# Placa_CLP_2021-08-01_15-21-18.net
KiCad netlist of a schematic drawn in EasyEDA
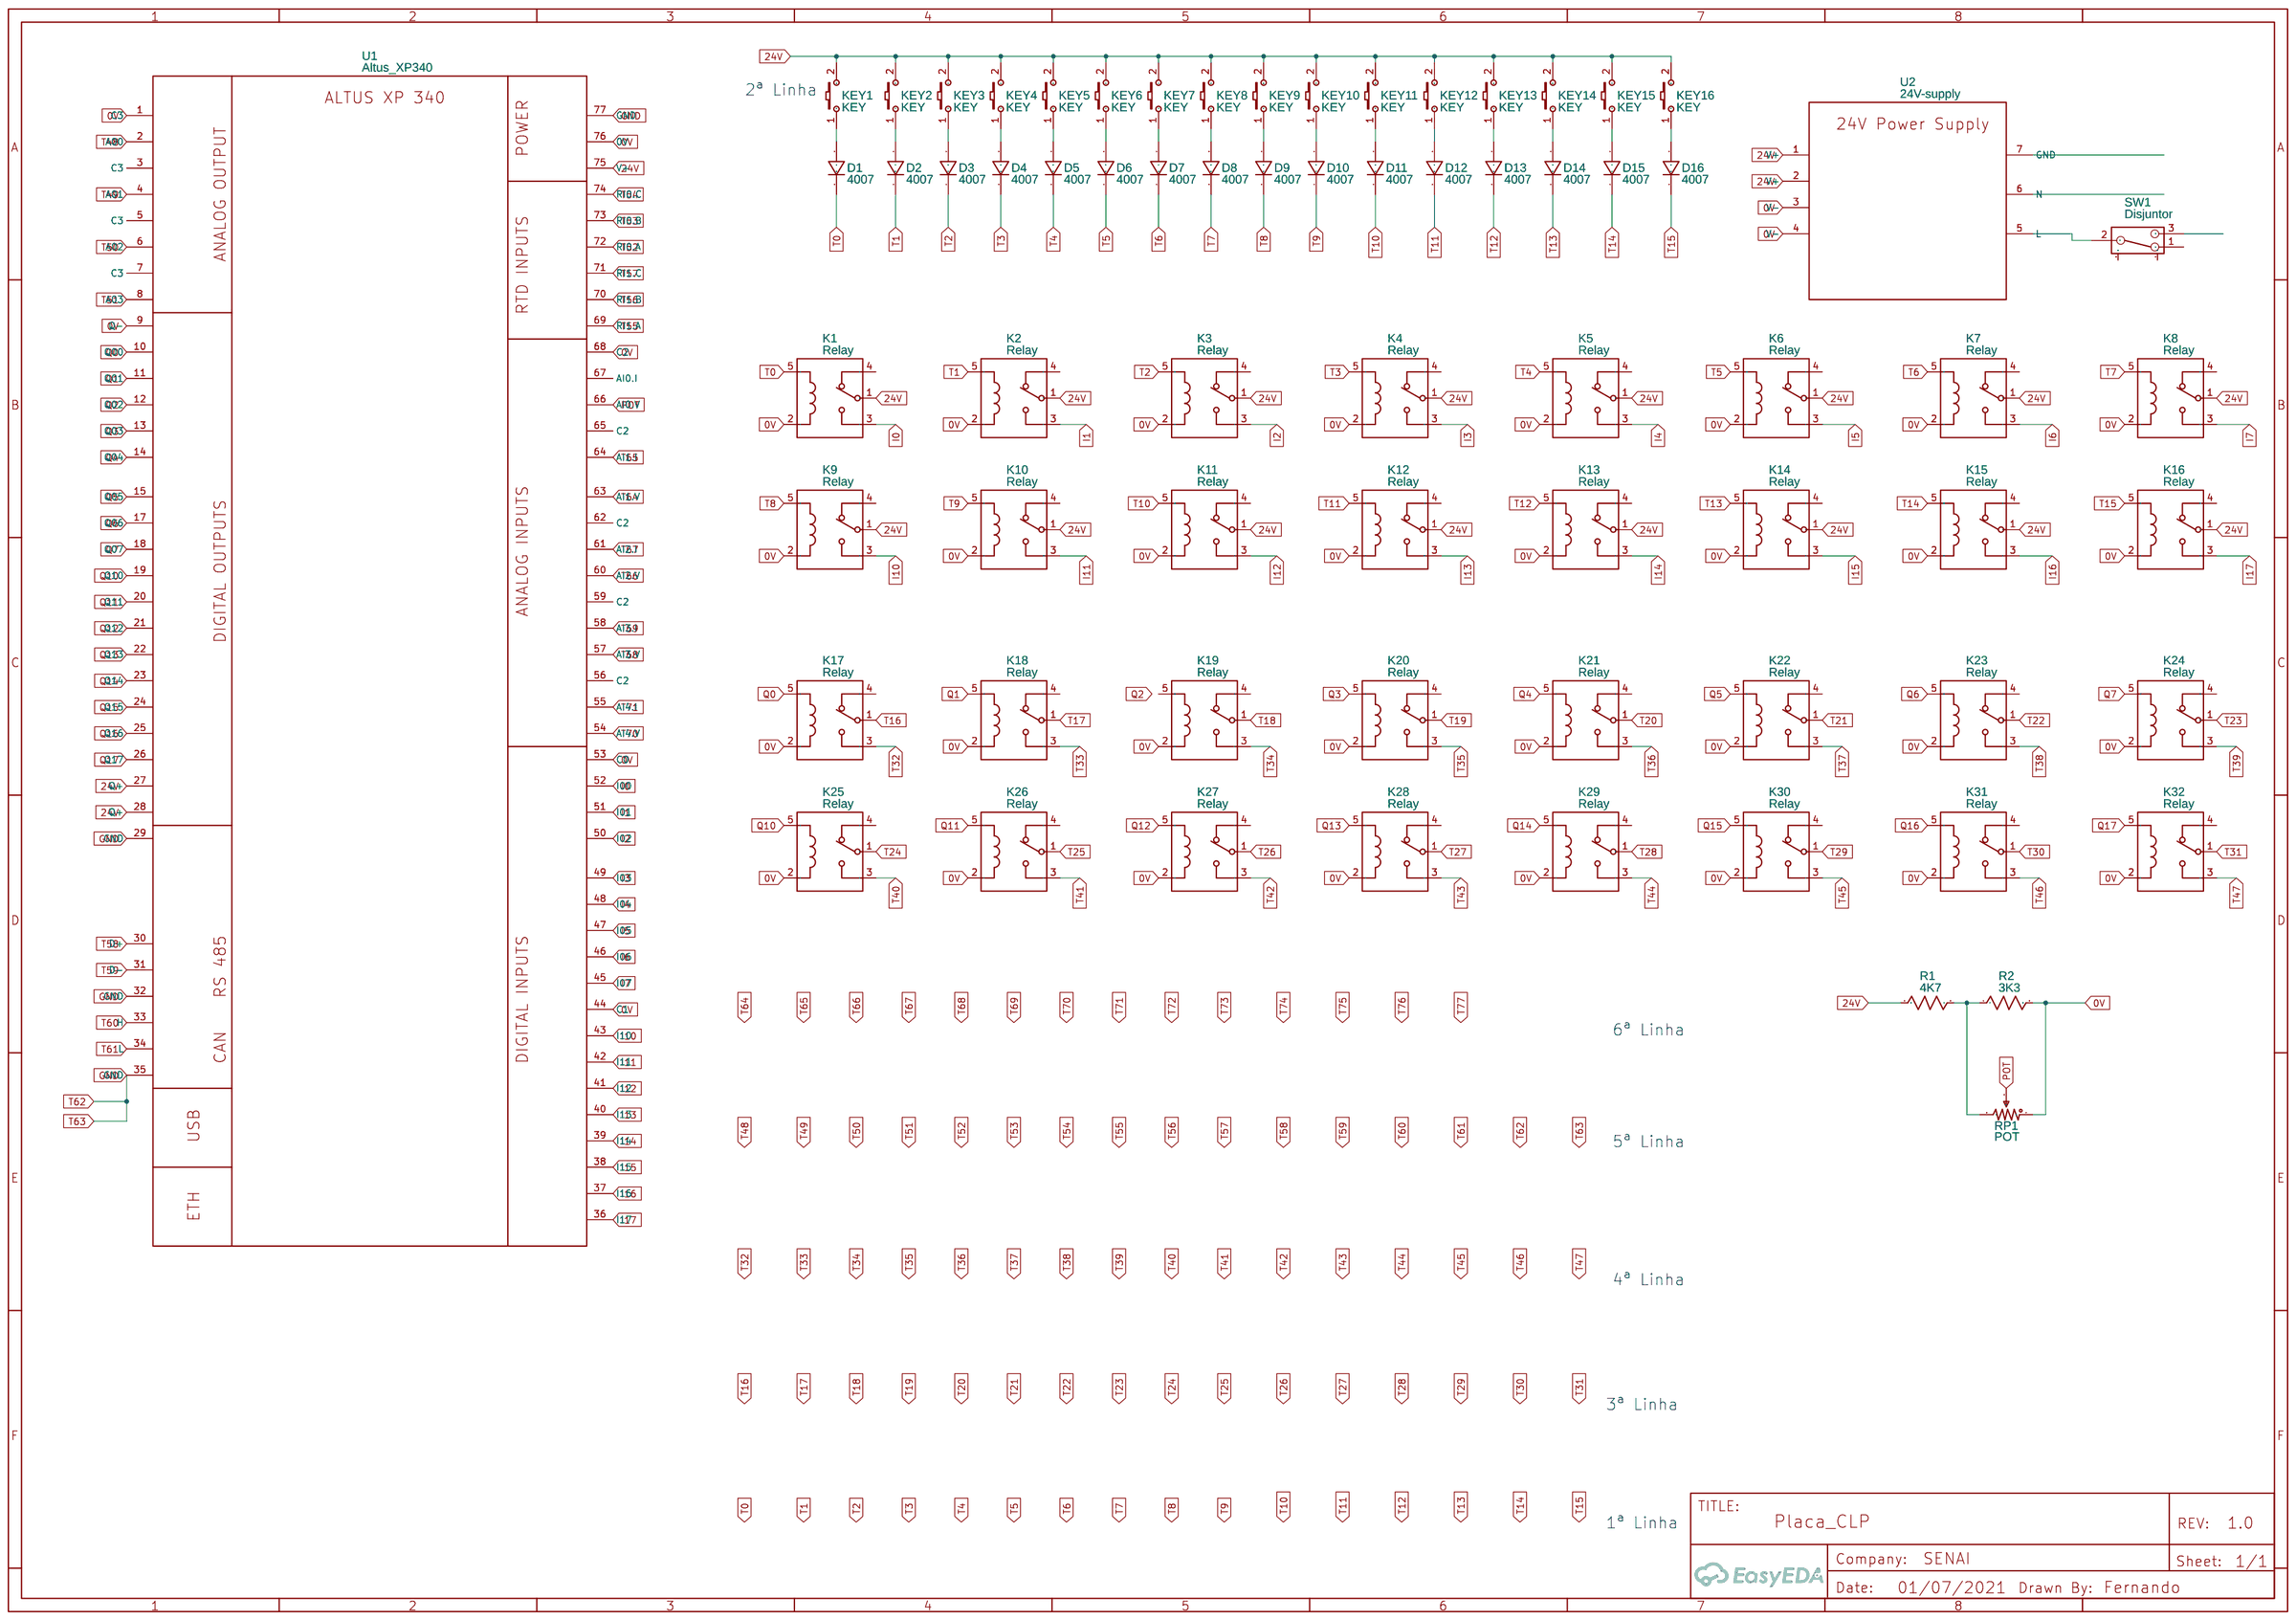
[diagram p0: schematic sheet]

(export (version "E")
  (design (tool "Eeschema 10.0.6"))
  (components
    (comp (ref "D1")
      (value "4007")
      (fields (field (name "BOM_Manufacturer Part") "1N4007") (field (name "BOM_Supplier Part") "C106903"))
      (libsource (lib "") (part "1N4007"))
    )
    (comp (ref "D2")
      (value "4007")
      (fields (field (name "BOM_Manufacturer Part") "1N4007") (field (name "BOM_Supplier Part") "C106903"))
      (libsource (lib "") (part "1N4007"))
    )
    (comp (ref "D3")
      (value "4007")
      (fields (field (name "BOM_Manufacturer Part") "1N4007") (field (name "BOM_Supplier Part") "C106903"))
      (libsource (lib "") (part "1N4007"))
    )
    (comp (ref "D4")
      (value "4007")
      (fields (field (name "BOM_Manufacturer Part") "1N4007") (field (name "BOM_Supplier Part") "C106903"))
      (libsource (lib "") (part "1N4007"))
    )
    (comp (ref "D5")
      (value "4007")
      (fields (field (name "BOM_Manufacturer Part") "1N4007") (field (name "BOM_Supplier Part") "C106903"))
      (libsource (lib "") (part "1N4007"))
    )
    (comp (ref "D6")
      (value "4007")
      (fields (field (name "BOM_Manufacturer Part") "1N4007") (field (name "BOM_Supplier Part") "C106903"))
      (libsource (lib "") (part "1N4007"))
    )
    (comp (ref "D7")
      (value "4007")
      (fields (field (name "BOM_Manufacturer Part") "1N4007") (field (name "BOM_Supplier Part") "C106903"))
      (libsource (lib "") (part "1N4007"))
    )
    (comp (ref "D8")
      (value "4007")
      (fields (field (name "BOM_Manufacturer Part") "1N4007") (field (name "BOM_Supplier Part") "C106903"))
      (libsource (lib "") (part "1N4007"))
    )
    (comp (ref "D9")
      (value "4007")
      (fields (field (name "BOM_Manufacturer Part") "1N4007") (field (name "BOM_Supplier Part") "C106903"))
      (libsource (lib "") (part "1N4007"))
    )
    (comp (ref "D10")
      (value "4007")
      (fields (field (name "BOM_Manufacturer Part") "1N4007") (field (name "BOM_Supplier Part") "C106903"))
      (libsource (lib "") (part "1N4007"))
    )
    (comp (ref "D11")
      (value "4007")
      (fields (field (name "BOM_Manufacturer Part") "1N4007") (field (name "BOM_Supplier Part") "C106903"))
      (libsource (lib "") (part "1N4007"))
    )
    (comp (ref "D12")
      (value "4007")
      (fields (field (name "BOM_Manufacturer Part") "1N4007") (field (name "BOM_Supplier Part") "C106903"))
      (libsource (lib "") (part "1N4007"))
    )
    (comp (ref "D13")
      (value "4007")
      (fields (field (name "BOM_Manufacturer Part") "1N4007") (field (name "BOM_Supplier Part") "C106903"))
      (libsource (lib "") (part "1N4007"))
    )
    (comp (ref "D14")
      (value "4007")
      (fields (field (name "BOM_Manufacturer Part") "1N4007") (field (name "BOM_Supplier Part") "C106903"))
      (libsource (lib "") (part "1N4007"))
    )
    (comp (ref "D15")
      (value "4007")
      (fields (field (name "BOM_Manufacturer Part") "1N4007") (field (name "BOM_Supplier Part") "C106903"))
      (libsource (lib "") (part "1N4007"))
    )
    (comp (ref "D16")
      (value "4007")
      (fields (field (name "BOM_Manufacturer Part") "1N4007") (field (name "BOM_Supplier Part") "C106903"))
      (libsource (lib "") (part "1N4007"))
    )
    (comp (ref "K1")
      (value "Relay")
      (fields
        (field (name "BOM_Manufacturer Part") "RelayHT3F-12VDC-SHG")
        (field (name "BOM_Supplier Part") "C22022")
      )
      (libsource (lib "") (part "RelayHT3F-12VDC-SHG"))
    )
    (comp (ref "K2")
      (value "Relay")
      (fields
        (field (name "BOM_Manufacturer Part") "RelayHT3F-12VDC-SHG")
        (field (name "BOM_Supplier Part") "C22022")
      )
      (libsource (lib "") (part "RelayHT3F-12VDC-SHG"))
    )
    (comp (ref "K3")
      (value "Relay")
      (fields
        (field (name "BOM_Manufacturer Part") "RelayHT3F-12VDC-SHG")
        (field (name "BOM_Supplier Part") "C22022")
      )
      (libsource (lib "") (part "RelayHT3F-12VDC-SHG"))
    )
    (comp (ref "K4")
      (value "Relay")
      (fields
        (field (name "BOM_Manufacturer Part") "RelayHT3F-12VDC-SHG")
        (field (name "BOM_Supplier Part") "C22022")
      )
      (libsource (lib "") (part "RelayHT3F-12VDC-SHG"))
    )
    (comp (ref "K5")
      (value "Relay")
      (fields
        (field (name "BOM_Manufacturer Part") "RelayHT3F-12VDC-SHG")
        (field (name "BOM_Supplier Part") "C22022")
      )
      (libsource (lib "") (part "RelayHT3F-12VDC-SHG"))
    )
    (comp (ref "K6")
      (value "Relay")
      (fields
        (field (name "BOM_Manufacturer Part") "RelayHT3F-12VDC-SHG")
        (field (name "BOM_Supplier Part") "C22022")
      )
      (libsource (lib "") (part "RelayHT3F-12VDC-SHG"))
    )
    (comp (ref "K7")
      (value "Relay")
      (fields
        (field (name "BOM_Manufacturer Part") "RelayHT3F-12VDC-SHG")
        (field (name "BOM_Supplier Part") "C22022")
      )
      (libsource (lib "") (part "RelayHT3F-12VDC-SHG"))
    )
    (comp (ref "K8")
      (value "Relay")
      (fields
        (field (name "BOM_Manufacturer Part") "RelayHT3F-12VDC-SHG")
        (field (name "BOM_Supplier Part") "C22022")
      )
      (libsource (lib "") (part "RelayHT3F-12VDC-SHG"))
    )
    (comp (ref "K9")
      (value "Relay")
      (fields
        (field (name "BOM_Manufacturer Part") "RelayHT3F-12VDC-SHG")
        (field (name "BOM_Supplier Part") "C22022")
      )
      (libsource (lib "") (part "RelayHT3F-12VDC-SHG"))
    )
    (comp (ref "K10")
      (value "Relay")
      (fields
        (field (name "BOM_Manufacturer Part") "RelayHT3F-12VDC-SHG")
        (field (name "BOM_Supplier Part") "C22022")
      )
      (libsource (lib "") (part "RelayHT3F-12VDC-SHG"))
    )
    (comp (ref "K11")
      (value "Relay")
      (fields
        (field (name "BOM_Manufacturer Part") "RelayHT3F-12VDC-SHG")
        (field (name "BOM_Supplier Part") "C22022")
      )
      (libsource (lib "") (part "RelayHT3F-12VDC-SHG"))
    )
    (comp (ref "K12")
      (value "Relay")
      (fields
        (field (name "BOM_Manufacturer Part") "RelayHT3F-12VDC-SHG")
        (field (name "BOM_Supplier Part") "C22022")
      )
      (libsource (lib "") (part "RelayHT3F-12VDC-SHG"))
    )
    (comp (ref "K13")
      (value "Relay")
      (fields
        (field (name "BOM_Manufacturer Part") "RelayHT3F-12VDC-SHG")
        (field (name "BOM_Supplier Part") "C22022")
      )
      (libsource (lib "") (part "RelayHT3F-12VDC-SHG"))
    )
    (comp (ref "K14")
      (value "Relay")
      (fields
        (field (name "BOM_Manufacturer Part") "RelayHT3F-12VDC-SHG")
        (field (name "BOM_Supplier Part") "C22022")
      )
      (libsource (lib "") (part "RelayHT3F-12VDC-SHG"))
    )
    (comp (ref "K15")
      (value "Relay")
      (fields
        (field (name "BOM_Manufacturer Part") "RelayHT3F-12VDC-SHG")
        (field (name "BOM_Supplier Part") "C22022")
      )
      (libsource (lib "") (part "RelayHT3F-12VDC-SHG"))
    )
    (comp (ref "K16")
      (value "Relay")
      (fields
        (field (name "BOM_Manufacturer Part") "RelayHT3F-12VDC-SHG")
        (field (name "BOM_Supplier Part") "C22022")
      )
      (libsource (lib "") (part "RelayHT3F-12VDC-SHG"))
    )
    (comp (ref "K17")
      (value "Relay")
      (fields
        (field (name "BOM_Manufacturer Part") "RelayHT3F-12VDC-SHG")
        (field (name "BOM_Supplier Part") "C22022")
      )
      (libsource (lib "") (part "RelayHT3F-12VDC-SHG"))
    )
    (comp (ref "K18")
      (value "Relay")
      (fields
        (field (name "BOM_Manufacturer Part") "RelayHT3F-12VDC-SHG")
        (field (name "BOM_Supplier Part") "C22022")
      )
      (libsource (lib "") (part "RelayHT3F-12VDC-SHG"))
    )
    (comp (ref "K19")
      (value "Relay")
      (fields
        (field (name "BOM_Manufacturer Part") "RelayHT3F-12VDC-SHG")
        (field (name "BOM_Supplier Part") "C22022")
      )
      (libsource (lib "") (part "RelayHT3F-12VDC-SHG"))
    )
    (comp (ref "K20")
      (value "Relay")
      (fields
        (field (name "BOM_Manufacturer Part") "RelayHT3F-12VDC-SHG")
        (field (name "BOM_Supplier Part") "C22022")
      )
      (libsource (lib "") (part "RelayHT3F-12VDC-SHG"))
    )
    (comp (ref "K21")
      (value "Relay")
      (fields
        (field (name "BOM_Manufacturer Part") "RelayHT3F-12VDC-SHG")
        (field (name "BOM_Supplier Part") "C22022")
      )
      (libsource (lib "") (part "RelayHT3F-12VDC-SHG"))
    )
    (comp (ref "K22")
      (value "Relay")
      (fields
        (field (name "BOM_Manufacturer Part") "RelayHT3F-12VDC-SHG")
        (field (name "BOM_Supplier Part") "C22022")
      )
      (libsource (lib "") (part "RelayHT3F-12VDC-SHG"))
    )
    (comp (ref "K23")
      (value "Relay")
      (fields
        (field (name "BOM_Manufacturer Part") "RelayHT3F-12VDC-SHG")
        (field (name "BOM_Supplier Part") "C22022")
      )
      (libsource (lib "") (part "RelayHT3F-12VDC-SHG"))
    )
    (comp (ref "K24")
      (value "Relay")
      (fields
        (field (name "BOM_Manufacturer Part") "RelayHT3F-12VDC-SHG")
        (field (name "BOM_Supplier Part") "C22022")
      )
      (libsource (lib "") (part "RelayHT3F-12VDC-SHG"))
    )
    (comp (ref "K25")
      (value "Relay")
      (fields
        (field (name "BOM_Manufacturer Part") "RelayHT3F-12VDC-SHG")
        (field (name "BOM_Supplier Part") "C22022")
      )
      (libsource (lib "") (part "RelayHT3F-12VDC-SHG"))
    )
    (comp (ref "K26")
      (value "Relay")
      (fields
        (field (name "BOM_Manufacturer Part") "RelayHT3F-12VDC-SHG")
        (field (name "BOM_Supplier Part") "C22022")
      )
      (libsource (lib "") (part "RelayHT3F-12VDC-SHG"))
    )
    (comp (ref "K27")
      (value "Relay")
      (fields
        (field (name "BOM_Manufacturer Part") "RelayHT3F-12VDC-SHG")
        (field (name "BOM_Supplier Part") "C22022")
      )
      (libsource (lib "") (part "RelayHT3F-12VDC-SHG"))
    )
    (comp (ref "K28")
      (value "Relay")
      (fields
        (field (name "BOM_Manufacturer Part") "RelayHT3F-12VDC-SHG")
        (field (name "BOM_Supplier Part") "C22022")
      )
      (libsource (lib "") (part "RelayHT3F-12VDC-SHG"))
    )
    (comp (ref "K29")
      (value "Relay")
      (fields
        (field (name "BOM_Manufacturer Part") "RelayHT3F-12VDC-SHG")
        (field (name "BOM_Supplier Part") "C22022")
      )
      (libsource (lib "") (part "RelayHT3F-12VDC-SHG"))
    )
    (comp (ref "K30")
      (value "Relay")
      (fields
        (field (name "BOM_Manufacturer Part") "RelayHT3F-12VDC-SHG")
        (field (name "BOM_Supplier Part") "C22022")
      )
      (libsource (lib "") (part "RelayHT3F-12VDC-SHG"))
    )
    (comp (ref "K31")
      (value "Relay")
      (fields
        (field (name "BOM_Manufacturer Part") "RelayHT3F-12VDC-SHG")
        (field (name "BOM_Supplier Part") "C22022")
      )
      (libsource (lib "") (part "RelayHT3F-12VDC-SHG"))
    )
    (comp (ref "K32")
      (value "Relay")
      (fields
        (field (name "BOM_Manufacturer Part") "RelayHT3F-12VDC-SHG")
        (field (name "BOM_Supplier Part") "C22022")
      )
      (libsource (lib "") (part "RelayHT3F-12VDC-SHG"))
    )
    (comp (ref "KEY1")
      (value "KEY")
      (fields
        (field (name "BOM_Manufacturer Part") "K2-1107ST-A4SW-06")
        (field (name "BOM_Supplier Part") "C118141")
      )
      (libsource (lib "") (part "K2-3.6×6.1_SMD"))
    )
    (comp (ref "KEY2")
      (value "KEY")
      (fields
        (field (name "BOM_Manufacturer Part") "K2-1107ST-A4SW-06")
        (field (name "BOM_Supplier Part") "C118141")
      )
      (libsource (lib "") (part "K2-3.6×6.1_SMD"))
    )
    (comp (ref "KEY3")
      (value "KEY")
      (fields
        (field (name "BOM_Manufacturer Part") "K2-1107ST-A4SW-06")
        (field (name "BOM_Supplier Part") "C118141")
      )
      (libsource (lib "") (part "K2-3.6×6.1_SMD"))
    )
    (comp (ref "KEY4")
      (value "KEY")
      (fields
        (field (name "BOM_Manufacturer Part") "K2-1107ST-A4SW-06")
        (field (name "BOM_Supplier Part") "C118141")
      )
      (libsource (lib "") (part "K2-3.6×6.1_SMD"))
    )
    (comp (ref "KEY5")
      (value "KEY")
      (fields
        (field (name "BOM_Manufacturer Part") "K2-1107ST-A4SW-06")
        (field (name "BOM_Supplier Part") "C118141")
      )
      (libsource (lib "") (part "K2-3.6×6.1_SMD"))
    )
    (comp (ref "KEY6")
      (value "KEY")
      (fields
        (field (name "BOM_Manufacturer Part") "K2-1107ST-A4SW-06")
        (field (name "BOM_Supplier Part") "C118141")
      )
      (libsource (lib "") (part "K2-3.6×6.1_SMD"))
    )
    (comp (ref "KEY7")
      (value "KEY")
      (fields
        (field (name "BOM_Manufacturer Part") "K2-1107ST-A4SW-06")
        (field (name "BOM_Supplier Part") "C118141")
      )
      (libsource (lib "") (part "K2-3.6×6.1_SMD"))
    )
    (comp (ref "KEY8")
      (value "KEY")
      (fields
        (field (name "BOM_Manufacturer Part") "K2-1107ST-A4SW-06")
        (field (name "BOM_Supplier Part") "C118141")
      )
      (libsource (lib "") (part "K2-3.6×6.1_SMD"))
    )
    (comp (ref "KEY9")
      (value "KEY")
      (fields
        (field (name "BOM_Manufacturer Part") "K2-1107ST-A4SW-06")
        (field (name "BOM_Supplier Part") "C118141")
      )
      (libsource (lib "") (part "K2-3.6×6.1_SMD"))
    )
    (comp (ref "KEY10")
      (value "KEY")
      (fields
        (field (name "BOM_Manufacturer Part") "K2-1107ST-A4SW-06")
        (field (name "BOM_Supplier Part") "C118141")
      )
      (libsource (lib "") (part "K2-3.6×6.1_SMD"))
    )
    (comp (ref "KEY11")
      (value "KEY")
      (fields
        (field (name "BOM_Manufacturer Part") "K2-1107ST-A4SW-06")
        (field (name "BOM_Supplier Part") "C118141")
      )
      (libsource (lib "") (part "K2-3.6×6.1_SMD"))
    )
    (comp (ref "KEY12")
      (value "KEY")
      (fields
        (field (name "BOM_Manufacturer Part") "K2-1107ST-A4SW-06")
        (field (name "BOM_Supplier Part") "C118141")
      )
      (libsource (lib "") (part "K2-3.6×6.1_SMD"))
    )
    (comp (ref "KEY13")
      (value "KEY")
      (fields
        (field (name "BOM_Manufacturer Part") "K2-1107ST-A4SW-06")
        (field (name "BOM_Supplier Part") "C118141")
      )
      (libsource (lib "") (part "K2-3.6×6.1_SMD"))
    )
    (comp (ref "KEY14")
      (value "KEY")
      (fields
        (field (name "BOM_Manufacturer Part") "K2-1107ST-A4SW-06")
        (field (name "BOM_Supplier Part") "C118141")
      )
      (libsource (lib "") (part "K2-3.6×6.1_SMD"))
    )
    (comp (ref "KEY15")
      (value "KEY")
      (fields
        (field (name "BOM_Manufacturer Part") "K2-1107ST-A4SW-06")
        (field (name "BOM_Supplier Part") "C118141")
      )
      (libsource (lib "") (part "K2-3.6×6.1_SMD"))
    )
    (comp (ref "KEY16")
      (value "KEY")
      (fields
        (field (name "BOM_Manufacturer Part") "K2-1107ST-A4SW-06")
        (field (name "BOM_Supplier Part") "C118141")
      )
      (libsource (lib "") (part "K2-3.6×6.1_SMD"))
    )
    (comp (ref "R1") (value "4K7") (libsource (lib "") (part "R_0603_US")))
    (comp (ref "R2") (value "3K3") (libsource (lib "") (part "R_0603_US")))
    (comp (ref "RP1") (value "POT") (libsource (lib "") (part "R_3386P_US")))
    (comp (ref "SW1")
      (value "Disjuntor")
      (fields
        (field (name "BOM_Manufacturer Part") "SK-12D02-VG5")
        (field (name "BOM_Supplier Part") "C136722")
      )
      (libsource (lib "") (part "SK-12D02-VG5"))
    )
    (comp (ref "U1") (value "Altus_XP340") (libsource (lib "") (part "Altus_XP340")))
    (comp (ref "U2") (value "24V-supply") (libsource (lib "") (part "24V-supply")))
  )
  (nets
    (net (code "1") (name "0V") (class "Default")
      (node (ref "K1") (pin "2") (pinfunction "2_2") (pintype "unspecified"))
      (node (ref "K10") (pin "2") (pinfunction "2_2") (pintype "unspecified"))
      (node (ref "K11") (pin "2") (pinfunction "2_2") (pintype "unspecified"))
      (node (ref "K12") (pin "2") (pinfunction "2_2") (pintype "unspecified"))
      (node (ref "K13") (pin "2") (pinfunction "2_2") (pintype "unspecified"))
      (node (ref "K14") (pin "2") (pinfunction "2_2") (pintype "unspecified"))
      (node (ref "K15") (pin "2") (pinfunction "2_2") (pintype "unspecified"))
      (node (ref "K16") (pin "2") (pinfunction "2_2") (pintype "unspecified"))
      (node (ref "K17") (pin "2") (pinfunction "2_2") (pintype "unspecified"))
      (node (ref "K18") (pin "2") (pinfunction "2_2") (pintype "unspecified"))
      (node (ref "K19") (pin "2") (pinfunction "2_2") (pintype "unspecified"))
      (node (ref "K2") (pin "2") (pinfunction "2_2") (pintype "unspecified"))
      (node (ref "K20") (pin "2") (pinfunction "2_2") (pintype "unspecified"))
      (node (ref "K21") (pin "2") (pinfunction "2_2") (pintype "unspecified"))
      (node (ref "K22") (pin "2") (pinfunction "2_2") (pintype "unspecified"))
      (node (ref "K23") (pin "2") (pinfunction "2_2") (pintype "unspecified"))
      (node (ref "K24") (pin "2") (pinfunction "2_2") (pintype "unspecified"))
      (node (ref "K25") (pin "2") (pinfunction "2_2") (pintype "unspecified"))
      (node (ref "K26") (pin "2") (pinfunction "2_2") (pintype "unspecified"))
      (node (ref "K27") (pin "2") (pinfunction "2_2") (pintype "unspecified"))
      (node (ref "K28") (pin "2") (pinfunction "2_2") (pintype "unspecified"))
      (node (ref "K29") (pin "2") (pinfunction "2_2") (pintype "unspecified"))
      (node (ref "K3") (pin "2") (pinfunction "2_2") (pintype "unspecified"))
      (node (ref "K30") (pin "2") (pinfunction "2_2") (pintype "unspecified"))
      (node (ref "K31") (pin "2") (pinfunction "2_2") (pintype "unspecified"))
      (node (ref "K32") (pin "2") (pinfunction "2_2") (pintype "unspecified"))
      (node (ref "K4") (pin "2") (pinfunction "2_2") (pintype "unspecified"))
      (node (ref "K5") (pin "2") (pinfunction "2_2") (pintype "unspecified"))
      (node (ref "K6") (pin "2") (pinfunction "2_2") (pintype "unspecified"))
      (node (ref "K7") (pin "2") (pinfunction "2_2") (pintype "unspecified"))
      (node (ref "K8") (pin "2") (pinfunction "2_2") (pintype "unspecified"))
      (node (ref "K9") (pin "2") (pinfunction "2_2") (pintype "unspecified"))
      (node (ref "R2") (pin "2") (pinfunction "2_2") (pintype "unspecified"))
      (node (ref "RP1") (pin "1") (pinfunction "1_1") (pintype "unspecified"))
    )
    (net (code "2") (name "24V") (class "Default")
      (node (ref "K1") (pin "1") (pinfunction "1_1") (pintype "unspecified"))
      (node (ref "K10") (pin "1") (pinfunction "1_1") (pintype "unspecified"))
      (node (ref "K11") (pin "1") (pinfunction "1_1") (pintype "unspecified"))
      (node (ref "K12") (pin "1") (pinfunction "1_1") (pintype "unspecified"))
      (node (ref "K13") (pin "1") (pinfunction "1_1") (pintype "unspecified"))
      (node (ref "K14") (pin "1") (pinfunction "1_1") (pintype "unspecified"))
      (node (ref "K15") (pin "1") (pinfunction "1_1") (pintype "unspecified"))
      (node (ref "K16") (pin "1") (pinfunction "1_1") (pintype "unspecified"))
      (node (ref "K2") (pin "1") (pinfunction "1_1") (pintype "unspecified"))
      (node (ref "K3") (pin "1") (pinfunction "1_1") (pintype "unspecified"))
      (node (ref "K4") (pin "1") (pinfunction "1_1") (pintype "unspecified"))
      (node (ref "K5") (pin "1") (pinfunction "1_1") (pintype "unspecified"))
      (node (ref "K6") (pin "1") (pinfunction "1_1") (pintype "unspecified"))
      (node (ref "K7") (pin "1") (pinfunction "1_1") (pintype "unspecified"))
      (node (ref "K8") (pin "1") (pinfunction "1_1") (pintype "unspecified"))
      (node (ref "K9") (pin "1") (pinfunction "1_1") (pintype "unspecified"))
      (node (ref "KEY1") (pin "2") (pinfunction "2_2") (pintype "unspecified"))
      (node (ref "KEY10") (pin "2") (pinfunction "2_2") (pintype "unspecified"))
      (node (ref "KEY11") (pin "2") (pinfunction "2_2") (pintype "unspecified"))
      (node (ref "KEY12") (pin "2") (pinfunction "2_2") (pintype "unspecified"))
      (node (ref "KEY13") (pin "2") (pinfunction "2_2") (pintype "unspecified"))
      (node (ref "KEY14") (pin "2") (pinfunction "2_2") (pintype "unspecified"))
      (node (ref "KEY15") (pin "2") (pinfunction "2_2") (pintype "unspecified"))
      (node (ref "KEY16") (pin "2") (pinfunction "2_2") (pintype "unspecified"))
      (node (ref "KEY2") (pin "2") (pinfunction "2_2") (pintype "unspecified"))
      (node (ref "KEY3") (pin "2") (pinfunction "2_2") (pintype "unspecified"))
      (node (ref "KEY4") (pin "2") (pinfunction "2_2") (pintype "unspecified"))
      (node (ref "KEY5") (pin "2") (pinfunction "2_2") (pintype "unspecified"))
      (node (ref "KEY6") (pin "2") (pinfunction "2_2") (pintype "unspecified"))
      (node (ref "KEY7") (pin "2") (pinfunction "2_2") (pintype "unspecified"))
      (node (ref "KEY8") (pin "2") (pinfunction "2_2") (pintype "unspecified"))
      (node (ref "KEY9") (pin "2") (pinfunction "2_2") (pintype "unspecified"))
      (node (ref "R1") (pin "1") (pinfunction "1_1") (pintype "unspecified"))
    )
    (net (code "4") (name "I0") (class "Default")
      (node (ref "K1") (pin "3") (pinfunction "3_3") (pintype "unspecified"))
    )
    (net (code "5") (name "I1") (class "Default")
      (node (ref "K2") (pin "3") (pinfunction "3_3") (pintype "unspecified"))
    )
    (net (code "6") (name "I2") (class "Default")
      (node (ref "K3") (pin "3") (pinfunction "3_3") (pintype "unspecified"))
    )
    (net (code "7") (name "I3") (class "Default")
      (node (ref "K4") (pin "3") (pinfunction "3_3") (pintype "unspecified"))
    )
    (net (code "8") (name "I4") (class "Default")
      (node (ref "K5") (pin "3") (pinfunction "3_3") (pintype "unspecified"))
    )
    (net (code "9") (name "I5") (class "Default")
      (node (ref "K6") (pin "3") (pinfunction "3_3") (pintype "unspecified"))
    )
    (net (code "10") (name "I6") (class "Default")
      (node (ref "K7") (pin "3") (pinfunction "3_3") (pintype "unspecified"))
    )
    (net (code "11") (name "I7") (class "Default")
      (node (ref "K8") (pin "3") (pinfunction "3_3") (pintype "unspecified"))
    )
    (net (code "12") (name "I10") (class "Default")
      (node (ref "K9") (pin "3") (pinfunction "3_3") (pintype "unspecified"))
    )
    (net (code "13") (name "I11") (class "Default")
      (node (ref "K10") (pin "3") (pinfunction "3_3") (pintype "unspecified"))
    )
    (net (code "14") (name "I12") (class "Default")
      (node (ref "K11") (pin "3") (pinfunction "3_3") (pintype "unspecified"))
    )
    (net (code "15") (name "I13") (class "Default")
      (node (ref "K12") (pin "3") (pinfunction "3_3") (pintype "unspecified"))
    )
    (net (code "16") (name "I14") (class "Default")
      (node (ref "K13") (pin "3") (pinfunction "3_3") (pintype "unspecified"))
    )
    (net (code "17") (name "I15") (class "Default")
      (node (ref "K14") (pin "3") (pinfunction "3_3") (pintype "unspecified"))
    )
    (net (code "18") (name "I16") (class "Default")
      (node (ref "K15") (pin "3") (pinfunction "3_3") (pintype "unspecified"))
    )
    (net (code "19") (name "I17") (class "Default")
      (node (ref "K16") (pin "3") (pinfunction "3_3") (pintype "unspecified"))
    )
    (net (code "20") (name "Net-(D1-Pad2)") (class "Default")
      (node (ref "D1") (pin "2") (pinfunction "2_2") (pintype "unspecified"))
      (node (ref "KEY1") (pin "1") (pinfunction "1_1") (pintype "unspecified"))
    )
    (net (code "21") (name "Net-(D2-Pad2)") (class "Default")
      (node (ref "D2") (pin "2") (pinfunction "2_2") (pintype "unspecified"))
      (node (ref "KEY2") (pin "1") (pinfunction "1_1") (pintype "unspecified"))
    )
    (net (code "22") (name "Net-(D3-Pad2)") (class "Default")
      (node (ref "D3") (pin "2") (pinfunction "2_2") (pintype "unspecified"))
      (node (ref "KEY3") (pin "1") (pinfunction "1_1") (pintype "unspecified"))
    )
    (net (code "23") (name "Net-(D4-Pad2)") (class "Default")
      (node (ref "D4") (pin "2") (pinfunction "2_2") (pintype "unspecified"))
      (node (ref "KEY4") (pin "1") (pinfunction "1_1") (pintype "unspecified"))
    )
    (net (code "24") (name "Net-(D5-Pad2)") (class "Default")
      (node (ref "D5") (pin "2") (pinfunction "2_2") (pintype "unspecified"))
      (node (ref "KEY5") (pin "1") (pinfunction "1_1") (pintype "unspecified"))
    )
    (net (code "25") (name "Net-(D6-Pad2)") (class "Default")
      (node (ref "D6") (pin "2") (pinfunction "2_2") (pintype "unspecified"))
      (node (ref "KEY6") (pin "1") (pinfunction "1_1") (pintype "unspecified"))
    )
    (net (code "26") (name "Net-(D7-Pad2)") (class "Default")
      (node (ref "D7") (pin "2") (pinfunction "2_2") (pintype "unspecified"))
      (node (ref "KEY7") (pin "1") (pinfunction "1_1") (pintype "unspecified"))
    )
    (net (code "27") (name "Net-(D8-Pad2)") (class "Default")
      (node (ref "D8") (pin "2") (pinfunction "2_2") (pintype "unspecified"))
      (node (ref "KEY8") (pin "1") (pinfunction "1_1") (pintype "unspecified"))
    )
    (net (code "28") (name "Net-(D9-Pad2)") (class "Default")
      (node (ref "D9") (pin "2") (pinfunction "2_2") (pintype "unspecified"))
      (node (ref "KEY9") (pin "1") (pinfunction "1_1") (pintype "unspecified"))
    )
    (net (code "29") (name "Net-(D10-Pad2)") (class "Default")
      (node (ref "D10") (pin "2") (pinfunction "2_2") (pintype "unspecified"))
      (node (ref "KEY10") (pin "1") (pinfunction "1_1") (pintype "unspecified"))
    )
    (net (code "30") (name "Net-(D11-Pad2)") (class "Default")
      (node (ref "D11") (pin "2") (pinfunction "2_2") (pintype "unspecified"))
      (node (ref "KEY11") (pin "1") (pinfunction "1_1") (pintype "unspecified"))
    )
    (net (code "31") (name "Net-(D12-Pad2)") (class "Default")
      (node (ref "D12") (pin "2") (pinfunction "2_2") (pintype "unspecified"))
      (node (ref "KEY12") (pin "1") (pinfunction "1_1") (pintype "unspecified"))
    )
    (net (code "32") (name "Net-(D13-Pad2)") (class "Default")
      (node (ref "D13") (pin "2") (pinfunction "2_2") (pintype "unspecified"))
      (node (ref "KEY13") (pin "1") (pinfunction "1_1") (pintype "unspecified"))
    )
    (net (code "33") (name "Net-(D14-Pad2)") (class "Default")
      (node (ref "D14") (pin "2") (pinfunction "2_2") (pintype "unspecified"))
      (node (ref "KEY14") (pin "1") (pinfunction "1_1") (pintype "unspecified"))
    )
    (net (code "34") (name "Net-(D15-Pad2)") (class "Default")
      (node (ref "D15") (pin "2") (pinfunction "2_2") (pintype "unspecified"))
      (node (ref "KEY15") (pin "1") (pinfunction "1_1") (pintype "unspecified"))
    )
    (net (code "35") (name "Net-(D16-Pad2)") (class "Default")
      (node (ref "D16") (pin "2") (pinfunction "2_2") (pintype "unspecified"))
      (node (ref "KEY16") (pin "1") (pinfunction "1_1") (pintype "unspecified"))
    )
    (net (code "36") (name "Net-(R1-Pad2)") (class "Default")
      (node (ref "R1") (pin "2") (pinfunction "2_2") (pintype "unspecified"))
      (node (ref "R2") (pin "1") (pinfunction "1_1") (pintype "unspecified"))
      (node (ref "RP1") (pin "3") (pinfunction "3_3") (pintype "unspecified"))
    )
    (net (code "37") (name "POT") (class "Default")
      (node (ref "RP1") (pin "2") (pinfunction "2_2") (pintype "unspecified"))
    )
    (net (code "38") (name "Q0") (class "Default")
      (node (ref "K17") (pin "5") (pinfunction "5_5") (pintype "unspecified"))
    )
    (net (code "39") (name "Q1") (class "Default")
      (node (ref "K18") (pin "5") (pinfunction "5_5") (pintype "unspecified"))
    )
    (net (code "41") (name "Q3") (class "Default")
      (node (ref "K20") (pin "5") (pinfunction "5_5") (pintype "unspecified"))
    )
    (net (code "42") (name "Q4") (class "Default")
      (node (ref "K21") (pin "5") (pinfunction "5_5") (pintype "unspecified"))
    )
    (net (code "43") (name "Q5") (class "Default")
      (node (ref "K22") (pin "5") (pinfunction "5_5") (pintype "unspecified"))
    )
    (net (code "44") (name "Q6") (class "Default")
      (node (ref "K23") (pin "5") (pinfunction "5_5") (pintype "unspecified"))
    )
    (net (code "45") (name "Q7") (class "Default")
      (node (ref "K24") (pin "5") (pinfunction "5_5") (pintype "unspecified"))
    )
    (net (code "46") (name "Q10") (class "Default")
      (node (ref "K25") (pin "5") (pinfunction "5_5") (pintype "unspecified"))
    )
    (net (code "47") (name "Q11") (class "Default")
      (node (ref "K26") (pin "5") (pinfunction "5_5") (pintype "unspecified"))
    )
    (net (code "48") (name "Q12") (class "Default")
      (node (ref "K27") (pin "5") (pinfunction "5_5") (pintype "unspecified"))
    )
    (net (code "49") (name "Q13") (class "Default")
      (node (ref "K28") (pin "5") (pinfunction "5_5") (pintype "unspecified"))
    )
    (net (code "50") (name "Q14") (class "Default")
      (node (ref "K29") (pin "5") (pinfunction "5_5") (pintype "unspecified"))
    )
    (net (code "51") (name "Q15") (class "Default")
      (node (ref "K30") (pin "5") (pinfunction "5_5") (pintype "unspecified"))
    )
    (net (code "52") (name "Q16") (class "Default")
      (node (ref "K31") (pin "5") (pinfunction "5_5") (pintype "unspecified"))
    )
    (net (code "53") (name "Q17") (class "Default")
      (node (ref "K32") (pin "5") (pinfunction "5_5") (pintype "unspecified"))
    )
    (net (code "54") (name "T0") (class "Default")
      (node (ref "D1") (pin "1") (pinfunction "1_1") (pintype "unspecified"))
      (node (ref "K1") (pin "5") (pinfunction "5_5") (pintype "unspecified"))
    )
    (net (code "55") (name "T1") (class "Default")
      (node (ref "D2") (pin "1") (pinfunction "1_1") (pintype "unspecified"))
      (node (ref "K2") (pin "5") (pinfunction "5_5") (pintype "unspecified"))
    )
    (net (code "56") (name "T2") (class "Default")
      (node (ref "D3") (pin "1") (pinfunction "1_1") (pintype "unspecified"))
      (node (ref "K3") (pin "5") (pinfunction "5_5") (pintype "unspecified"))
    )
    (net (code "57") (name "T3") (class "Default")
      (node (ref "D4") (pin "1") (pinfunction "1_1") (pintype "unspecified"))
      (node (ref "K4") (pin "5") (pinfunction "5_5") (pintype "unspecified"))
    )
    (net (code "58") (name "T4") (class "Default")
      (node (ref "D5") (pin "1") (pinfunction "1_1") (pintype "unspecified"))
      (node (ref "K5") (pin "5") (pinfunction "5_5") (pintype "unspecified"))
    )
    (net (code "59") (name "T5") (class "Default")
      (node (ref "D6") (pin "1") (pinfunction "1_1") (pintype "unspecified"))
      (node (ref "K6") (pin "5") (pinfunction "5_5") (pintype "unspecified"))
    )
    (net (code "60") (name "T6") (class "Default")
      (node (ref "D7") (pin "1") (pinfunction "1_1") (pintype "unspecified"))
      (node (ref "K7") (pin "5") (pinfunction "5_5") (pintype "unspecified"))
    )
    (net (code "61") (name "T7") (class "Default")
      (node (ref "D8") (pin "1") (pinfunction "1_1") (pintype "unspecified"))
      (node (ref "K8") (pin "5") (pinfunction "5_5") (pintype "unspecified"))
    )
    (net (code "62") (name "T8") (class "Default")
      (node (ref "D9") (pin "1") (pinfunction "1_1") (pintype "unspecified"))
      (node (ref "K9") (pin "5") (pinfunction "5_5") (pintype "unspecified"))
    )
    (net (code "63") (name "T9") (class "Default")
      (node (ref "D10") (pin "1") (pinfunction "1_1") (pintype "unspecified"))
      (node (ref "K10") (pin "5") (pinfunction "5_5") (pintype "unspecified"))
    )
    (net (code "64") (name "T10") (class "Default")
      (node (ref "D11") (pin "1") (pinfunction "1_1") (pintype "unspecified"))
      (node (ref "K11") (pin "5") (pinfunction "5_5") (pintype "unspecified"))
    )
    (net (code "65") (name "T11") (class "Default")
      (node (ref "D12") (pin "1") (pinfunction "1_1") (pintype "unspecified"))
      (node (ref "K12") (pin "5") (pinfunction "5_5") (pintype "unspecified"))
    )
    (net (code "66") (name "T12") (class "Default")
      (node (ref "D13") (pin "1") (pinfunction "1_1") (pintype "unspecified"))
      (node (ref "K13") (pin "5") (pinfunction "5_5") (pintype "unspecified"))
    )
    (net (code "67") (name "T13") (class "Default")
      (node (ref "D14") (pin "1") (pinfunction "1_1") (pintype "unspecified"))
      (node (ref "K14") (pin "5") (pinfunction "5_5") (pintype "unspecified"))
    )
    (net (code "68") (name "T14") (class "Default")
      (node (ref "D15") (pin "1") (pinfunction "1_1") (pintype "unspecified"))
      (node (ref "K15") (pin "5") (pinfunction "5_5") (pintype "unspecified"))
    )
    (net (code "69") (name "T15") (class "Default")
      (node (ref "D16") (pin "1") (pinfunction "1_1") (pintype "unspecified"))
      (node (ref "K16") (pin "5") (pinfunction "5_5") (pintype "unspecified"))
    )
    (net (code "70") (name "T16") (class "Default")
      (node (ref "K17") (pin "1") (pinfunction "1_1") (pintype "unspecified"))
    )
    (net (code "71") (name "T17") (class "Default")
      (node (ref "K18") (pin "1") (pinfunction "1_1") (pintype "unspecified"))
    )
    (net (code "72") (name "T18") (class "Default")
      (node (ref "K19") (pin "1") (pinfunction "1_1") (pintype "unspecified"))
    )
    (net (code "73") (name "T19") (class "Default")
      (node (ref "K20") (pin "1") (pinfunction "1_1") (pintype "unspecified"))
    )
    (net (code "74") (name "T20") (class "Default")
      (node (ref "K21") (pin "1") (pinfunction "1_1") (pintype "unspecified"))
    )
    (net (code "75") (name "T21") (class "Default")
      (node (ref "K22") (pin "1") (pinfunction "1_1") (pintype "unspecified"))
    )
    (net (code "76") (name "T22") (class "Default")
      (node (ref "K23") (pin "1") (pinfunction "1_1") (pintype "unspecified"))
    )
    (net (code "77") (name "T23") (class "Default")
      (node (ref "K24") (pin "1") (pinfunction "1_1") (pintype "unspecified"))
    )
    (net (code "78") (name "T24") (class "Default")
      (node (ref "K25") (pin "1") (pinfunction "1_1") (pintype "unspecified"))
    )
    (net (code "79") (name "T25") (class "Default")
      (node (ref "K26") (pin "1") (pinfunction "1_1") (pintype "unspecified"))
    )
    (net (code "80") (name "T26") (class "Default")
      (node (ref "K27") (pin "1") (pinfunction "1_1") (pintype "unspecified"))
    )
    (net (code "81") (name "T27") (class "Default")
      (node (ref "K28") (pin "1") (pinfunction "1_1") (pintype "unspecified"))
    )
    (net (code "82") (name "T28") (class "Default")
      (node (ref "K29") (pin "1") (pinfunction "1_1") (pintype "unspecified"))
    )
    (net (code "83") (name "T29") (class "Default")
      (node (ref "K30") (pin "1") (pinfunction "1_1") (pintype "unspecified"))
    )
    (net (code "84") (name "T30") (class "Default")
      (node (ref "K31") (pin "1") (pinfunction "1_1") (pintype "unspecified"))
    )
    (net (code "85") (name "T31") (class "Default")
      (node (ref "K32") (pin "1") (pinfunction "1_1") (pintype "unspecified"))
    )
    (net (code "86") (name "T32") (class "Default")
      (node (ref "K17") (pin "3") (pinfunction "3_3") (pintype "unspecified"))
    )
    (net (code "87") (name "T33") (class "Default")
      (node (ref "K18") (pin "3") (pinfunction "3_3") (pintype "unspecified"))
    )
    (net (code "88") (name "T34") (class "Default")
      (node (ref "K19") (pin "3") (pinfunction "3_3") (pintype "unspecified"))
    )
    (net (code "89") (name "T35") (class "Default")
      (node (ref "K20") (pin "3") (pinfunction "3_3") (pintype "unspecified"))
    )
    (net (code "90") (name "T36") (class "Default")
      (node (ref "K21") (pin "3") (pinfunction "3_3") (pintype "unspecified"))
    )
    (net (code "91") (name "T37") (class "Default")
      (node (ref "K22") (pin "3") (pinfunction "3_3") (pintype "unspecified"))
    )
    (net (code "92") (name "T38") (class "Default")
      (node (ref "K23") (pin "3") (pinfunction "3_3") (pintype "unspecified"))
    )
    (net (code "93") (name "T39") (class "Default")
      (node (ref "K24") (pin "3") (pinfunction "3_3") (pintype "unspecified"))
    )
    (net (code "94") (name "T40") (class "Default")
      (node (ref "K25") (pin "3") (pinfunction "3_3") (pintype "unspecified"))
    )
    (net (code "95") (name "T41") (class "Default")
      (node (ref "K26") (pin "3") (pinfunction "3_3") (pintype "unspecified"))
    )
    (net (code "96") (name "T42") (class "Default")
      (node (ref "K27") (pin "3") (pinfunction "3_3") (pintype "unspecified"))
    )
    (net (code "97") (name "T43") (class "Default")
      (node (ref "K28") (pin "3") (pinfunction "3_3") (pintype "unspecified"))
    )
    (net (code "98") (name "T44") (class "Default")
      (node (ref "K29") (pin "3") (pinfunction "3_3") (pintype "unspecified"))
    )
    (net (code "99") (name "T45") (class "Default")
      (node (ref "K30") (pin "3") (pinfunction "3_3") (pintype "unspecified"))
    )
    (net (code "100") (name "T46") (class "Default")
      (node (ref "K31") (pin "3") (pinfunction "3_3") (pintype "unspecified"))
    )
    (net (code "101") (name "T47") (class "Default")
      (node (ref "K32") (pin "3") (pinfunction "3_3") (pintype "unspecified"))
    )
    (net (code "130") (name "unconnected-(K1-Pad4)") (class "Default")
      (node (ref "K1") (pin "4") (pinfunction "4_4") (pintype "unspecified"))
    )
    (net (code "131") (name "unconnected-(K2-Pad4)") (class "Default")
      (node (ref "K2") (pin "4") (pinfunction "4_4") (pintype "unspecified"))
    )
    (net (code "132") (name "unconnected-(K3-Pad4)") (class "Default")
      (node (ref "K3") (pin "4") (pinfunction "4_4") (pintype "unspecified"))
    )
    (net (code "133") (name "unconnected-(K4-Pad4)") (class "Default")
      (node (ref "K4") (pin "4") (pinfunction "4_4") (pintype "unspecified"))
    )
    (net (code "134") (name "unconnected-(K5-Pad4)") (class "Default")
      (node (ref "K5") (pin "4") (pinfunction "4_4") (pintype "unspecified"))
    )
    (net (code "135") (name "unconnected-(K6-Pad4)") (class "Default")
      (node (ref "K6") (pin "4") (pinfunction "4_4") (pintype "unspecified"))
    )
    (net (code "136") (name "unconnected-(K7-Pad4)") (class "Default")
      (node (ref "K7") (pin "4") (pinfunction "4_4") (pintype "unspecified"))
    )
    (net (code "137") (name "unconnected-(K8-Pad4)") (class "Default")
      (node (ref "K8") (pin "4") (pinfunction "4_4") (pintype "unspecified"))
    )
    (net (code "138") (name "unconnected-(K9-Pad4)") (class "Default")
      (node (ref "K9") (pin "4") (pinfunction "4_4") (pintype "unspecified"))
    )
    (net (code "139") (name "unconnected-(K10-Pad4)") (class "Default")
      (node (ref "K10") (pin "4") (pinfunction "4_4") (pintype "unspecified"))
    )
    (net (code "140") (name "unconnected-(K11-Pad4)") (class "Default")
      (node (ref "K11") (pin "4") (pinfunction "4_4") (pintype "unspecified"))
    )
    (net (code "141") (name "unconnected-(K12-Pad4)") (class "Default")
      (node (ref "K12") (pin "4") (pinfunction "4_4") (pintype "unspecified"))
    )
    (net (code "142") (name "unconnected-(K13-Pad4)") (class "Default")
      (node (ref "K13") (pin "4") (pinfunction "4_4") (pintype "unspecified"))
    )
    (net (code "143") (name "unconnected-(K14-Pad4)") (class "Default")
      (node (ref "K14") (pin "4") (pinfunction "4_4") (pintype "unspecified"))
    )
    (net (code "144") (name "unconnected-(K15-Pad4)") (class "Default")
      (node (ref "K15") (pin "4") (pinfunction "4_4") (pintype "unspecified"))
    )
    (net (code "145") (name "unconnected-(K16-Pad4)") (class "Default")
      (node (ref "K16") (pin "4") (pinfunction "4_4") (pintype "unspecified"))
    )
    (net (code "146") (name "unconnected-(K17-Pad4)") (class "Default")
      (node (ref "K17") (pin "4") (pinfunction "4_4") (pintype "unspecified"))
    )
    (net (code "147") (name "unconnected-(K18-Pad4)") (class "Default")
      (node (ref "K18") (pin "4") (pinfunction "4_4") (pintype "unspecified"))
    )
    (net (code "148") (name "unconnected-(K19-Pad4)") (class "Default")
      (node (ref "K19") (pin "4") (pinfunction "4_4") (pintype "unspecified"))
    )
    (net (code "149") (name "unconnected-(K19-Pad5)") (class "Default")
      (node (ref "K19") (pin "5") (pinfunction "5_5") (pintype "unspecified"))
    )
    (net (code "150") (name "unconnected-(K20-Pad4)") (class "Default")
      (node (ref "K20") (pin "4") (pinfunction "4_4") (pintype "unspecified"))
    )
    (net (code "151") (name "unconnected-(K21-Pad4)") (class "Default")
      (node (ref "K21") (pin "4") (pinfunction "4_4") (pintype "unspecified"))
    )
    (net (code "152") (name "unconnected-(K22-Pad4)") (class "Default")
      (node (ref "K22") (pin "4") (pinfunction "4_4") (pintype "unspecified"))
    )
    (net (code "153") (name "unconnected-(K23-Pad4)") (class "Default")
      (node (ref "K23") (pin "4") (pinfunction "4_4") (pintype "unspecified"))
    )
    (net (code "154") (name "unconnected-(K24-Pad4)") (class "Default")
      (node (ref "K24") (pin "4") (pinfunction "4_4") (pintype "unspecified"))
    )
    (net (code "155") (name "unconnected-(K25-Pad4)") (class "Default")
      (node (ref "K25") (pin "4") (pinfunction "4_4") (pintype "unspecified"))
    )
    (net (code "156") (name "unconnected-(K26-Pad4)") (class "Default")
      (node (ref "K26") (pin "4") (pinfunction "4_4") (pintype "unspecified"))
    )
    (net (code "157") (name "unconnected-(K27-Pad4)") (class "Default")
      (node (ref "K27") (pin "4") (pinfunction "4_4") (pintype "unspecified"))
    )
    (net (code "158") (name "unconnected-(K28-Pad4)") (class "Default")
      (node (ref "K28") (pin "4") (pinfunction "4_4") (pintype "unspecified"))
    )
    (net (code "159") (name "unconnected-(K29-Pad4)") (class "Default")
      (node (ref "K29") (pin "4") (pinfunction "4_4") (pintype "unspecified"))
    )
    (net (code "160") (name "unconnected-(K30-Pad4)") (class "Default")
      (node (ref "K30") (pin "4") (pinfunction "4_4") (pintype "unspecified"))
    )
    (net (code "161") (name "unconnected-(K31-Pad4)") (class "Default")
      (node (ref "K31") (pin "4") (pinfunction "4_4") (pintype "unspecified"))
    )
    (net (code "162") (name "unconnected-(K32-Pad4)") (class "Default")
      (node (ref "K32") (pin "4") (pinfunction "4_4") (pintype "unspecified"))
    )
    (net (code "163") (name "unconnected-(SW1-Pad1)") (class "Default")
      (node (ref "SW1") (pin "1") (pinfunction "1_1") (pintype "unspecified"))
    )
    (net (code "164") (name "unconnected-(SW1-Pad2)") (class "Default")
      (node (ref "SW1") (pin "2") (pinfunction "2_2") (pintype "unspecified"))
    )
    (net (code "165") (name "unconnected-(SW1-Pad3)") (class "Default")
      (node (ref "SW1") (pin "3") (pinfunction "3_3") (pintype "unspecified"))
    )
    (net (code "166") (name "unconnected-(SW1-Pad4)") (class "Default")
      (node (ref "SW1") (pin "4") (pinfunction "4_4") (pintype "unspecified"))
    )
    (net (code "167") (name "unconnected-(SW1-Pad5)") (class "Default")
      (node (ref "SW1") (pin "5") (pinfunction "5_5") (pintype "unspecified"))
    )
    (net (code "168") (name "unconnected-(U1-0V-Pad76)") (class "Default")
      (node (ref "U1") (pin "76") (pinfunction "0V_76") (pintype "unspecified"))
    )
    (net (code "169") (name "unconnected-(U1-A00-Pad2)") (class "Default")
      (node (ref "U1") (pin "2") (pinfunction "A00_2") (pintype "unspecified"))
    )
    (net (code "170") (name "unconnected-(U1-A01-Pad4)") (class "Default")
      (node (ref "U1") (pin "4") (pinfunction "A01_4") (pintype "unspecified"))
    )
    (net (code "171") (name "unconnected-(U1-A02-Pad6)") (class "Default")
      (node (ref "U1") (pin "6") (pinfunction "A02_6") (pintype "unspecified"))
    )
    (net (code "172") (name "unconnected-(U1-A03-Pad8)") (class "Default")
      (node (ref "U1") (pin "8") (pinfunction "A03_8") (pintype "unspecified"))
    )
    (net (code "173") (name "unconnected-(U1-AI0.I-Pad67)") (class "Default")
      (node (ref "U1") (pin "67") (pinfunction "AI0.I_67") (pintype "unspecified"))
    )
    (net (code "174") (name "unconnected-(U1-AI0.V-Pad66)") (class "Default")
      (node (ref "U1") (pin "66") (pinfunction "AI0.V_66") (pintype "unspecified"))
    )
    (net (code "175") (name "unconnected-(U1-AI1.I-Pad64)") (class "Default")
      (node (ref "U1") (pin "64") (pinfunction "AI1.I_64") (pintype "unspecified"))
    )
    (net (code "176") (name "unconnected-(U1-AI1.V-Pad63)") (class "Default")
      (node (ref "U1") (pin "63") (pinfunction "AI1.V_63") (pintype "unspecified"))
    )
    (net (code "177") (name "unconnected-(U1-AI2.I-Pad61)") (class "Default")
      (node (ref "U1") (pin "61") (pinfunction "AI2.I_61") (pintype "unspecified"))
    )
    (net (code "178") (name "unconnected-(U1-AI2.V-Pad60)") (class "Default")
      (node (ref "U1") (pin "60") (pinfunction "AI2.V_60") (pintype "unspecified"))
    )
    (net (code "179") (name "unconnected-(U1-AI3.I-Pad58)") (class "Default")
      (node (ref "U1") (pin "58") (pinfunction "AI3.I_58") (pintype "unspecified"))
    )
    (net (code "180") (name "unconnected-(U1-AI3.V-Pad57)") (class "Default")
      (node (ref "U1") (pin "57") (pinfunction "AI3.V_57") (pintype "unspecified"))
    )
    (net (code "181") (name "unconnected-(U1-AI4.I-Pad55)") (class "Default")
      (node (ref "U1") (pin "55") (pinfunction "AI4.I_55") (pintype "unspecified"))
    )
    (net (code "182") (name "unconnected-(U1-AI4.V-Pad54)") (class "Default")
      (node (ref "U1") (pin "54") (pinfunction "AI4.V_54") (pintype "unspecified"))
    )
    (net (code "183") (name "unconnected-(U1-C0-Pad53)") (class "Default")
      (node (ref "U1") (pin "53") (pinfunction "C0_53") (pintype "unspecified"))
    )
    (net (code "184") (name "unconnected-(U1-C1-Pad44)") (class "Default")
      (node (ref "U1") (pin "44") (pinfunction "C1_44") (pintype "unspecified"))
    )
    (net (code "185") (name "unconnected-(U1-C2-Pad56)") (class "Default")
      (node (ref "U1") (pin "56") (pinfunction "C2_56") (pintype "unspecified"))
    )
    (net (code "186") (name "unconnected-(U1-C2-Pad59)") (class "Default")
      (node (ref "U1") (pin "59") (pinfunction "C2_59") (pintype "unspecified"))
    )
    (net (code "187") (name "unconnected-(U1-C2-Pad62)") (class "Default")
      (node (ref "U1") (pin "62") (pinfunction "C2_62") (pintype "unspecified"))
    )
    (net (code "188") (name "unconnected-(U1-C2-Pad65)") (class "Default")
      (node (ref "U1") (pin "65") (pinfunction "C2_65") (pintype "unspecified"))
    )
    (net (code "189") (name "unconnected-(U1-C2-Pad68)") (class "Default")
      (node (ref "U1") (pin "68") (pinfunction "C2_68") (pintype "unspecified"))
    )
    (net (code "190") (name "unconnected-(U1-C3-Pad1)") (class "Default")
      (node (ref "U1") (pin "1") (pinfunction "C3_1") (pintype "unspecified"))
    )
    (net (code "191") (name "unconnected-(U1-C3-Pad3)") (class "Default")
      (node (ref "U1") (pin "3") (pinfunction "C3_3") (pintype "unspecified"))
    )
    (net (code "192") (name "unconnected-(U1-C3-Pad5)") (class "Default")
      (node (ref "U1") (pin "5") (pinfunction "C3_5") (pintype "unspecified"))
    )
    (net (code "193") (name "unconnected-(U1-C3-Pad7)") (class "Default")
      (node (ref "U1") (pin "7") (pinfunction "C3_7") (pintype "unspecified"))
    )
    (net (code "194") (name "unconnected-(U1-D+-Pad30)") (class "Default")
      (node (ref "U1") (pin "30") (pinfunction "D+_30") (pintype "unspecified"))
    )
    (net (code "195") (name "unconnected-(U1-D--Pad31)") (class "Default")
      (node (ref "U1") (pin "31") (pinfunction "D-_31") (pintype "unspecified"))
    )
    (net (code "196") (name "unconnected-(U1-GND-Pad29)") (class "Default")
      (node (ref "U1") (pin "29") (pinfunction "GND_29") (pintype "unspecified"))
    )
    (net (code "197") (name "unconnected-(U1-GND-Pad32)") (class "Default")
      (node (ref "U1") (pin "32") (pinfunction "GND_32") (pintype "unspecified"))
    )
    (net (code "198") (name "unconnected-(U1-GND-Pad35)") (class "Default")
      (node (ref "U1") (pin "35") (pinfunction "GND_35") (pintype "unspecified"))
    )
    (net (code "199") (name "unconnected-(U1-GND-Pad77)") (class "Default")
      (node (ref "U1") (pin "77") (pinfunction "GND_77") (pintype "unspecified"))
    )
    (net (code "200") (name "unconnected-(U1-H-Pad33)") (class "Default")
      (node (ref "U1") (pin "33") (pinfunction "H_33") (pintype "unspecified"))
    )
    (net (code "201") (name "unconnected-(U1-I00-Pad52)") (class "Default")
      (node (ref "U1") (pin "52") (pinfunction "I00_52") (pintype "unspecified"))
    )
    (net (code "202") (name "unconnected-(U1-I01-Pad51)") (class "Default")
      (node (ref "U1") (pin "51") (pinfunction "I01_51") (pintype "unspecified"))
    )
    (net (code "203") (name "unconnected-(U1-I02-Pad50)") (class "Default")
      (node (ref "U1") (pin "50") (pinfunction "I02_50") (pintype "unspecified"))
    )
    (net (code "204") (name "unconnected-(U1-I03-Pad49)") (class "Default")
      (node (ref "U1") (pin "49") (pinfunction "I03_49") (pintype "unspecified"))
    )
    (net (code "205") (name "unconnected-(U1-I04-Pad48)") (class "Default")
      (node (ref "U1") (pin "48") (pinfunction "I04_48") (pintype "unspecified"))
    )
    (net (code "206") (name "unconnected-(U1-I05-Pad47)") (class "Default")
      (node (ref "U1") (pin "47") (pinfunction "I05_47") (pintype "unspecified"))
    )
    (net (code "207") (name "unconnected-(U1-I06-Pad46)") (class "Default")
      (node (ref "U1") (pin "46") (pinfunction "I06_46") (pintype "unspecified"))
    )
    (net (code "208") (name "unconnected-(U1-I07-Pad45)") (class "Default")
      (node (ref "U1") (pin "45") (pinfunction "I07_45") (pintype "unspecified"))
    )
    (net (code "209") (name "unconnected-(U1-I10-Pad43)") (class "Default")
      (node (ref "U1") (pin "43") (pinfunction "I10_43") (pintype "unspecified"))
    )
    (net (code "210") (name "unconnected-(U1-I11-Pad42)") (class "Default")
      (node (ref "U1") (pin "42") (pinfunction "I11_42") (pintype "unspecified"))
    )
    (net (code "211") (name "unconnected-(U1-I12-Pad41)") (class "Default")
      (node (ref "U1") (pin "41") (pinfunction "I12_41") (pintype "unspecified"))
    )
    (net (code "212") (name "unconnected-(U1-I13-Pad40)") (class "Default")
      (node (ref "U1") (pin "40") (pinfunction "I13_40") (pintype "unspecified"))
    )
    (net (code "213") (name "unconnected-(U1-I14-Pad39)") (class "Default")
      (node (ref "U1") (pin "39") (pinfunction "I14_39") (pintype "unspecified"))
    )
    (net (code "214") (name "unconnected-(U1-I15-Pad38)") (class "Default")
      (node (ref "U1") (pin "38") (pinfunction "I15_38") (pintype "unspecified"))
    )
    (net (code "215") (name "unconnected-(U1-I16-Pad37)") (class "Default")
      (node (ref "U1") (pin "37") (pinfunction "I16_37") (pintype "unspecified"))
    )
    (net (code "216") (name "unconnected-(U1-I17-Pad36)") (class "Default")
      (node (ref "U1") (pin "36") (pinfunction "I17_36") (pintype "unspecified"))
    )
    (net (code "217") (name "unconnected-(U1-L-Pad34)") (class "Default")
      (node (ref "U1") (pin "34") (pinfunction "L_34") (pintype "unspecified"))
    )
    (net (code "218") (name "unconnected-(U1-Q+-Pad27)") (class "Default")
      (node (ref "U1") (pin "27") (pinfunction "Q+_27") (pintype "unspecified"))
    )
    (net (code "219") (name "unconnected-(U1-Q+-Pad28)") (class "Default")
      (node (ref "U1") (pin "28") (pinfunction "Q+_28") (pintype "unspecified"))
    )
    (net (code "220") (name "unconnected-(U1-Q--Pad9)") (class "Default")
      (node (ref "U1") (pin "9") (pinfunction "Q-_9") (pintype "unspecified"))
    )
    (net (code "221") (name "unconnected-(U1-Q00-Pad10)") (class "Default")
      (node (ref "U1") (pin "10") (pinfunction "Q00_10") (pintype "unspecified"))
    )
    (net (code "222") (name "unconnected-(U1-Q01-Pad11)") (class "Default")
      (node (ref "U1") (pin "11") (pinfunction "Q01_11") (pintype "unspecified"))
    )
    (net (code "223") (name "unconnected-(U1-Q02-Pad12)") (class "Default")
      (node (ref "U1") (pin "12") (pinfunction "Q02_12") (pintype "unspecified"))
    )
    (net (code "224") (name "unconnected-(U1-Q03-Pad13)") (class "Default")
      (node (ref "U1") (pin "13") (pinfunction "Q03_13") (pintype "unspecified"))
    )
    (net (code "225") (name "unconnected-(U1-Q04-Pad14)") (class "Default")
      (node (ref "U1") (pin "14") (pinfunction "Q04_14") (pintype "unspecified"))
    )
    (net (code "226") (name "unconnected-(U1-Q05-Pad15)") (class "Default")
      (node (ref "U1") (pin "15") (pinfunction "Q05_15") (pintype "unspecified"))
    )
    (net (code "227") (name "unconnected-(U1-Q06-Pad17)") (class "Default")
      (node (ref "U1") (pin "17") (pinfunction "Q06_17") (pintype "unspecified"))
    )
    (net (code "228") (name "unconnected-(U1-Q07-Pad18)") (class "Default")
      (node (ref "U1") (pin "18") (pinfunction "Q07_18") (pintype "unspecified"))
    )
    (net (code "229") (name "unconnected-(U1-Q10-Pad19)") (class "Default")
      (node (ref "U1") (pin "19") (pinfunction "Q10_19") (pintype "unspecified"))
    )
    (net (code "230") (name "unconnected-(U1-Q11-Pad20)") (class "Default")
      (node (ref "U1") (pin "20") (pinfunction "Q11_20") (pintype "unspecified"))
    )
    (net (code "231") (name "unconnected-(U1-Q12-Pad21)") (class "Default")
      (node (ref "U1") (pin "21") (pinfunction "Q12_21") (pintype "unspecified"))
    )
    (net (code "232") (name "unconnected-(U1-Q13-Pad22)") (class "Default")
      (node (ref "U1") (pin "22") (pinfunction "Q13_22") (pintype "unspecified"))
    )
    (net (code "233") (name "unconnected-(U1-Q14-Pad23)") (class "Default")
      (node (ref "U1") (pin "23") (pinfunction "Q14_23") (pintype "unspecified"))
    )
    (net (code "234") (name "unconnected-(U1-Q15-Pad24)") (class "Default")
      (node (ref "U1") (pin "24") (pinfunction "Q15_24") (pintype "unspecified"))
    )
    (net (code "235") (name "unconnected-(U1-Q16-Pad25)") (class "Default")
      (node (ref "U1") (pin "25") (pinfunction "Q16_25") (pintype "unspecified"))
    )
    (net (code "236") (name "unconnected-(U1-Q17-Pad26)") (class "Default")
      (node (ref "U1") (pin "26") (pinfunction "Q17_26") (pintype "unspecified"))
    )
    (net (code "237") (name "unconnected-(U1-RI0.A-Pad72)") (class "Default")
      (node (ref "U1") (pin "72") (pinfunction "RI0.A_72") (pintype "unspecified"))
    )
    (net (code "238") (name "unconnected-(U1-RI0.B-Pad73)") (class "Default")
      (node (ref "U1") (pin "73") (pinfunction "RI0.B_73") (pintype "unspecified"))
    )
    (net (code "239") (name "unconnected-(U1-RI0.C-Pad74)") (class "Default")
      (node (ref "U1") (pin "74") (pinfunction "RI0.C_74") (pintype "unspecified"))
    )
    (net (code "240") (name "unconnected-(U1-RI1.A-Pad69)") (class "Default")
      (node (ref "U1") (pin "69") (pinfunction "RI1.A_69") (pintype "unspecified"))
    )
    (net (code "241") (name "unconnected-(U1-RI1.B-Pad70)") (class "Default")
      (node (ref "U1") (pin "70") (pinfunction "RI1.B_70") (pintype "unspecified"))
    )
    (net (code "242") (name "unconnected-(U1-RI1.C-Pad71)") (class "Default")
      (node (ref "U1") (pin "71") (pinfunction "RI1.C_71") (pintype "unspecified"))
    )
    (net (code "243") (name "unconnected-(U1-V+-Pad75)") (class "Default")
      (node (ref "U1") (pin "75") (pinfunction "V+_75") (pintype "unspecified"))
    )
    (net (code "244") (name "unconnected-(U2-GND-Pad7)") (class "Default")
      (node (ref "U2") (pin "7") (pinfunction "GND_7") (pintype "unspecified"))
    )
    (net (code "245") (name "unconnected-(U2-L-Pad5)") (class "Default")
      (node (ref "U2") (pin "5") (pinfunction "L_5") (pintype "unspecified"))
    )
    (net (code "246") (name "unconnected-(U2-N-Pad6)") (class "Default")
      (node (ref "U2") (pin "6") (pinfunction "N_6") (pintype "unspecified"))
    )
    (net (code "247") (name "unconnected-(U2-V+-Pad1)") (class "Default")
      (node (ref "U2") (pin "1") (pinfunction "V+_1") (pintype "unspecified"))
    )
    (net (code "248") (name "unconnected-(U2-V+-Pad2)") (class "Default")
      (node (ref "U2") (pin "2") (pinfunction "V+_2") (pintype "unspecified"))
    )
    (net (code "249") (name "unconnected-(U2-V--Pad3)") (class "Default")
      (node (ref "U2") (pin "3") (pinfunction "V-_3") (pintype "unspecified"))
    )
    (net (code "250") (name "unconnected-(U2-V--Pad4)") (class "Default")
      (node (ref "U2") (pin "4") (pinfunction "V-_4") (pintype "unspecified"))
    )
  )
)
